# InkTime_schematic.net
KiCad netlist of a schematic drawn in EAGLE
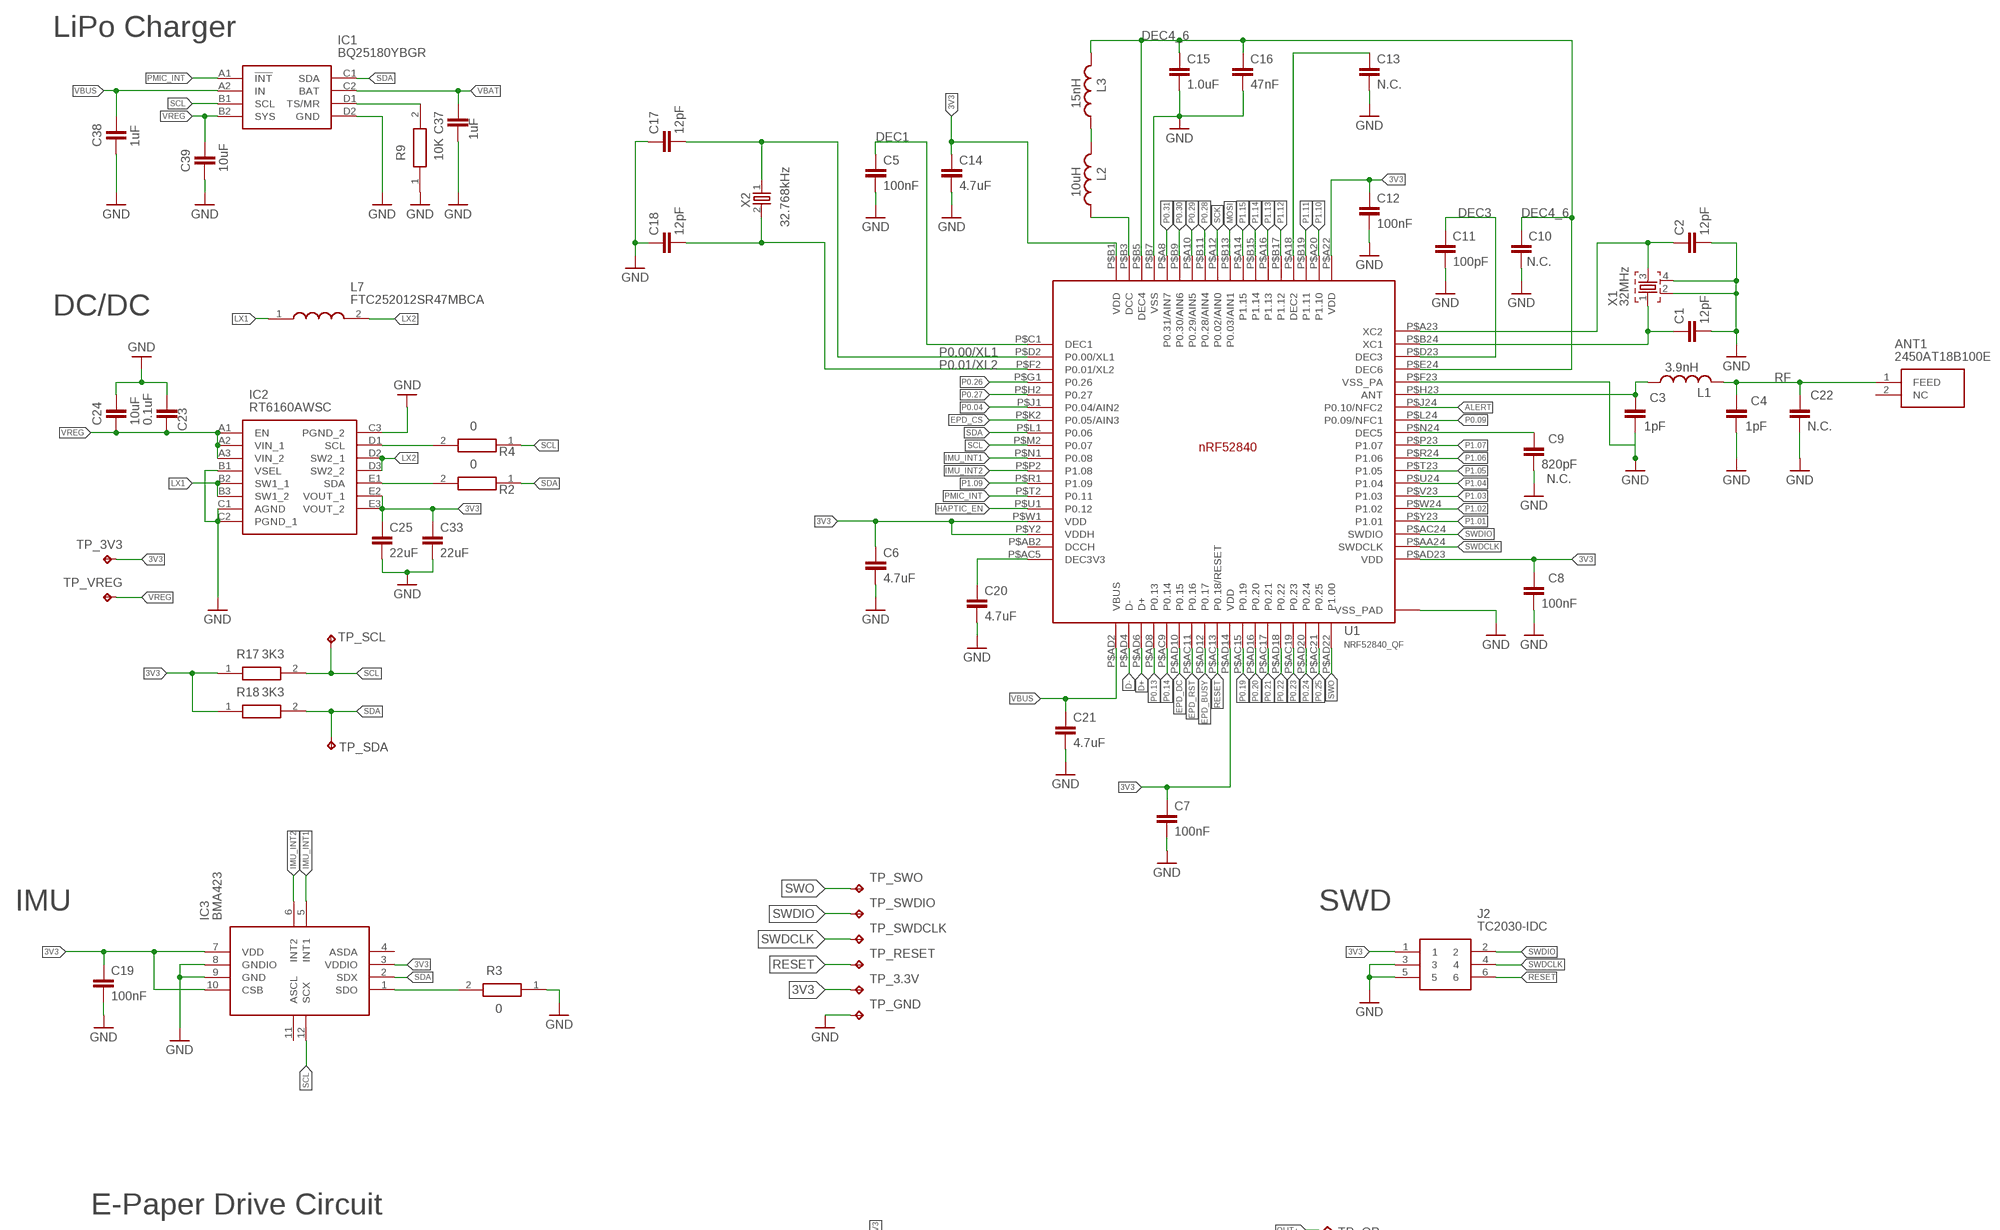
[diagram p0: schematic, sheet 1, part 1 of 2]
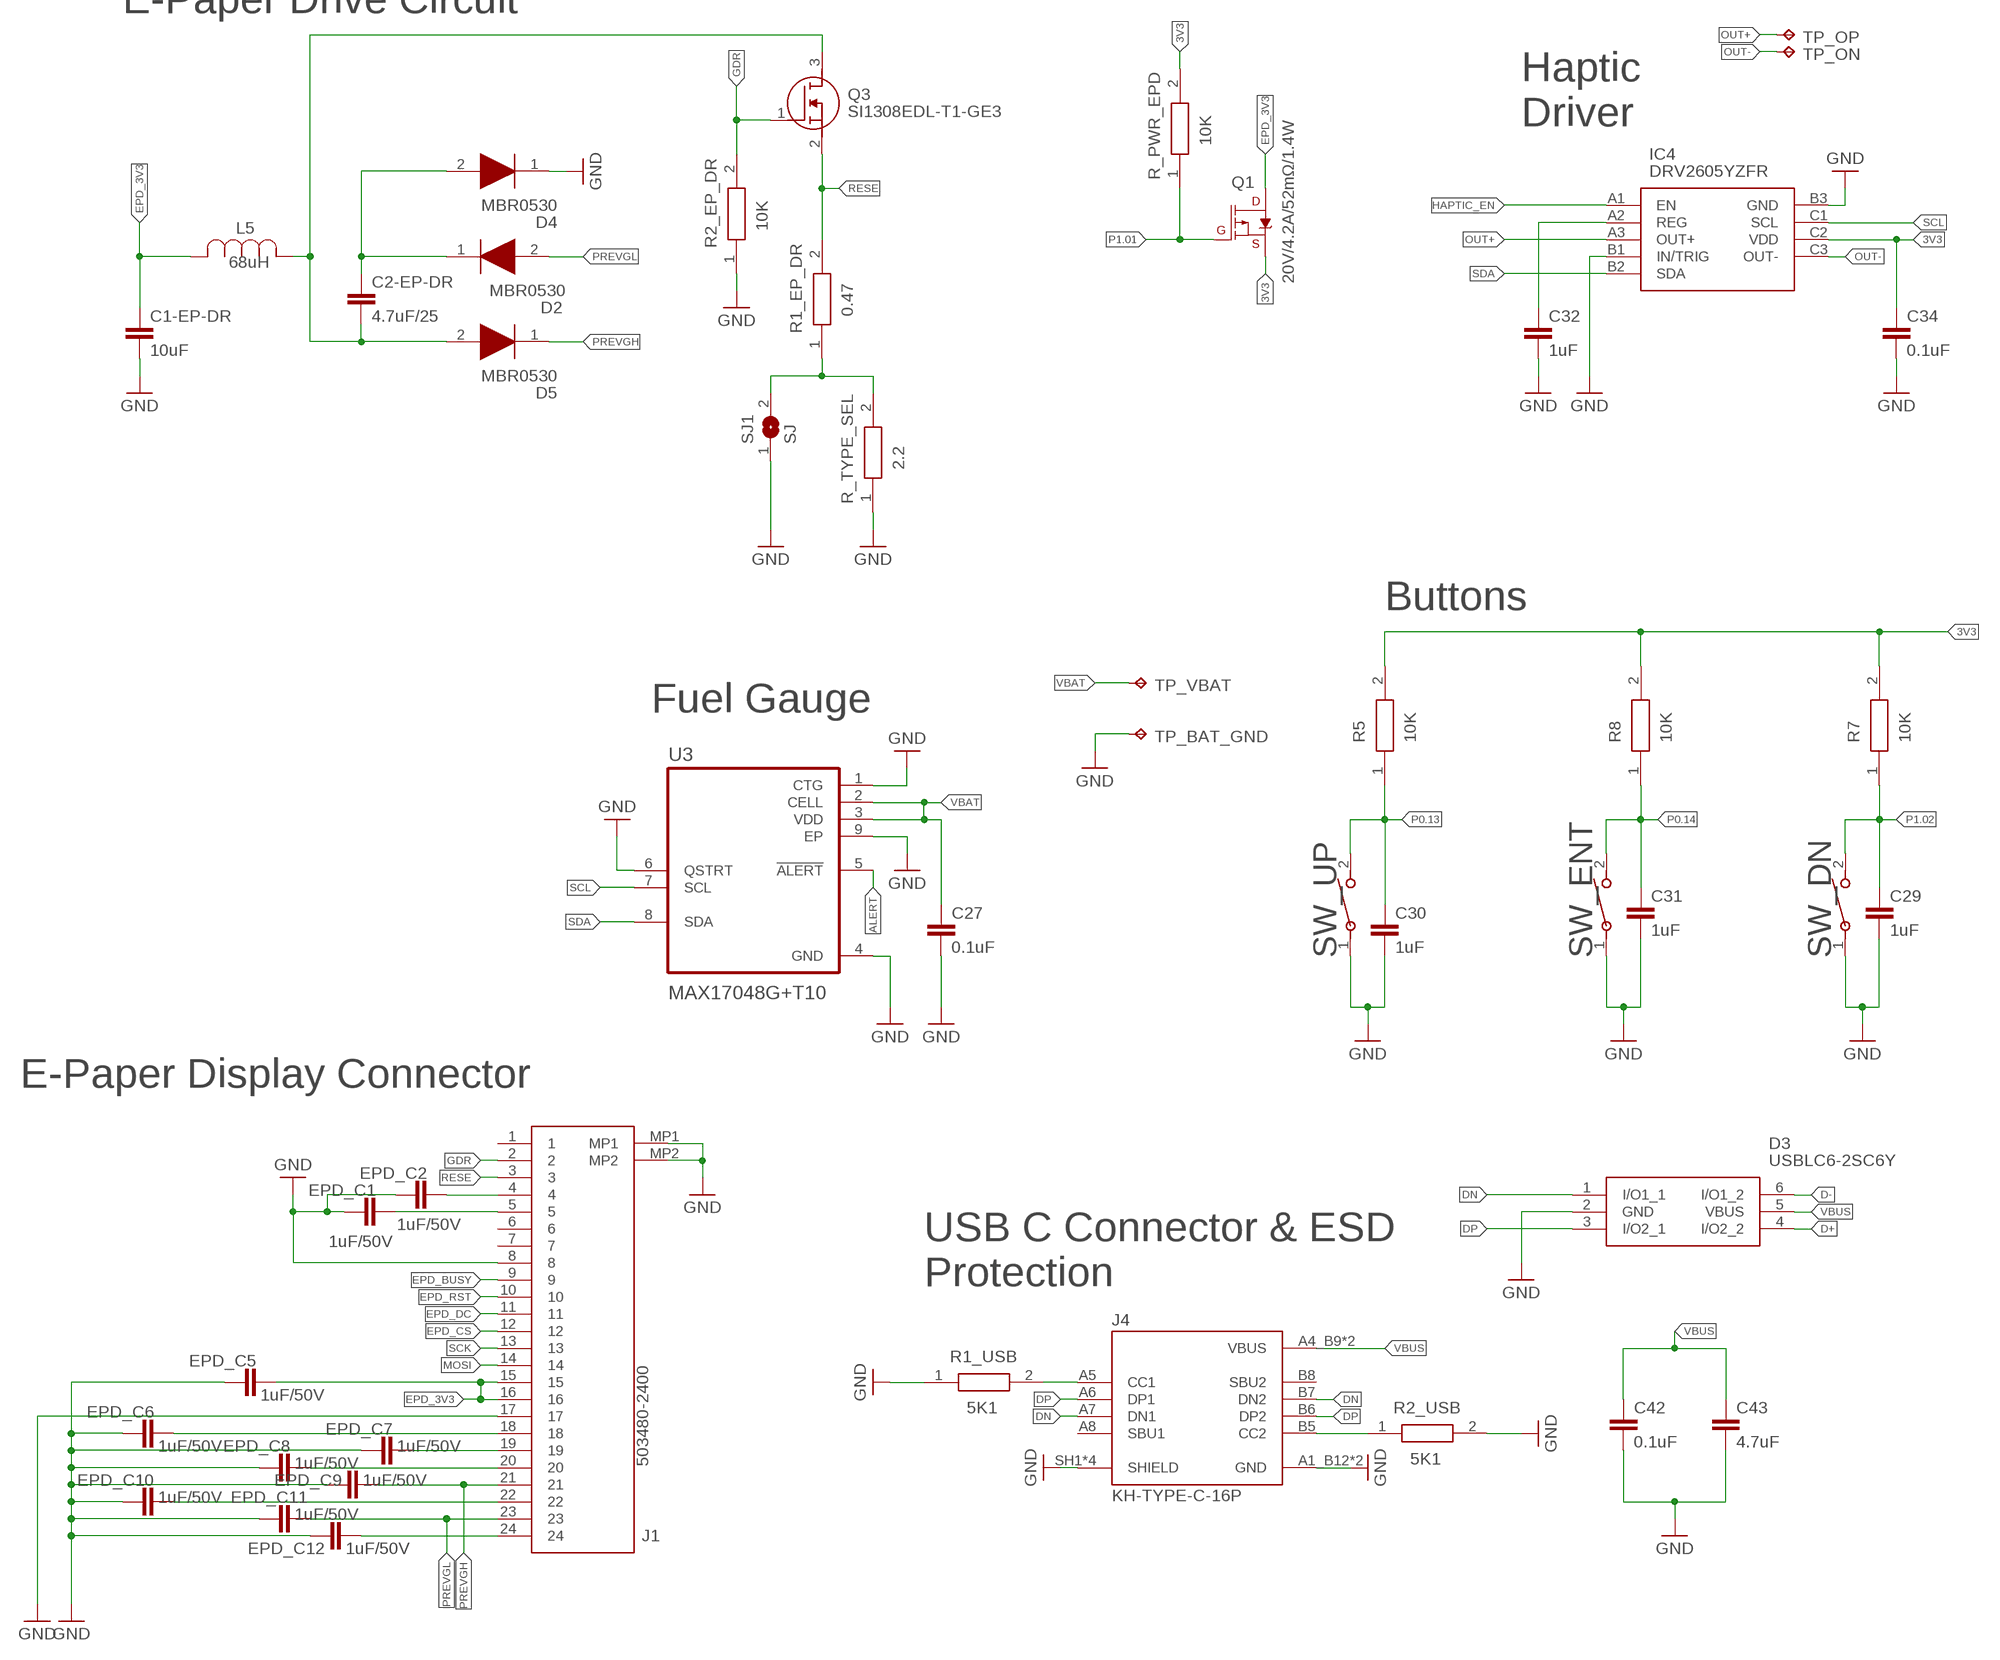
[diagram p1: schematic, sheet 1, part 2 of 2]

(export (version "E")
  (design (tool "Eeschema 10.0.6"))
  (components
    (comp (ref "ANT1")
      (value "2450AT18B100E")
      (footprint "eagle-import:2450AT18B100E_ANTC3216X140N")
      (fields (field (name "MOUSER_PART_NUMBER") "609-2450AT18B100E"))
      (libsource (lib "eagle-import") (part "2450AT18B100E_2450AT18B100E"))
    )
    (comp (ref "C1")
      (value "12pF")
      (footprint "eagle-import:NORDIC_NRF_3_RESC0201_N")
      (libsource (lib "eagle-import") (part "NORDIC_NRF_3_CAPACITOR_0201_N"))
    )
    (comp (ref "C1-EP-DR")
      (value "10uF")
      (footprint "eagle-import:NORDIC_NRF_3_RESC0402_N")
      (libsource (lib "eagle-import") (part "NORDIC_NRF_3_CAPACITOR_0402_N"))
    )
    (comp (ref "C2")
      (value "12pF")
      (footprint "eagle-import:NORDIC_NRF_3_RESC0201_N")
      (libsource (lib "eagle-import") (part "NORDIC_NRF_3_CAPACITOR_0201_N"))
    )
    (comp (ref "C2-EP-DR")
      (value "4.7uF/25")
      (footprint "eagle-import:NORDIC_NRF_3_RESC0603_N")
      (libsource (lib "eagle-import") (part "NORDIC_NRF_3_CAPACITOR_0603_N"))
    )
    (comp (ref "C3")
      (value "1pF")
      (footprint "eagle-import:NORDIC_NRF_3_RESC0201_N")
      (libsource (lib "eagle-import") (part "NORDIC_NRF_3_CAPACITOR_0201_N"))
    )
    (comp (ref "C4")
      (value "1pF")
      (footprint "eagle-import:NORDIC_NRF_3_RESC0201_N")
      (libsource (lib "eagle-import") (part "NORDIC_NRF_3_CAPACITOR_0201_N"))
    )
    (comp (ref "C5")
      (value "100nF")
      (footprint "eagle-import:NORDIC_NRF_3_RESC0201_N")
      (libsource (lib "eagle-import") (part "NORDIC_NRF_3_CAPACITOR_0201_N"))
    )
    (comp (ref "C6")
      (value "4.7uF")
      (footprint "eagle-import:NORDIC_NRF_3_RESC0402_N")
      (libsource (lib "eagle-import") (part "NORDIC_NRF_3_CAPACITOR_0402_N"))
    )
    (comp (ref "C7")
      (value "100nF")
      (footprint "eagle-import:NORDIC_NRF_3_RESC0201_N")
      (libsource (lib "eagle-import") (part "NORDIC_NRF_3_CAPACITOR_0201_N"))
    )
    (comp (ref "C8")
      (value "100nF")
      (footprint "eagle-import:NORDIC_NRF_3_RESC0201_N")
      (libsource (lib "eagle-import") (part "NORDIC_NRF_3_CAPACITOR_0201_N"))
    )
    (comp (ref "C9")
      (value "820pF")
      (footprint "eagle-import:NORDIC_NRF_3_RESC0201_N")
      (libsource (lib "eagle-import") (part "NORDIC_NRF_3_CAPACITOR_0201_N"))
    )
    (comp (ref "C10")
      (value "N.C.")
      (footprint "eagle-import:NORDIC_NRF_3_RESC0201_N")
      (libsource (lib "eagle-import") (part "NORDIC_NRF_3_CAPACITOR_0201_N"))
    )
    (comp (ref "C11")
      (value "100pF")
      (footprint "eagle-import:NORDIC_NRF_3_RESC0201_N")
      (libsource (lib "eagle-import") (part "NORDIC_NRF_3_CAPACITOR_0201_N"))
    )
    (comp (ref "C12")
      (value "100nF")
      (footprint "eagle-import:NORDIC_NRF_3_RESC0201_N")
      (libsource (lib "eagle-import") (part "NORDIC_NRF_3_CAPACITOR_0201_N"))
    )
    (comp (ref "C13")
      (value "N.C.")
      (footprint "eagle-import:NORDIC_NRF_3_RESC0201_N")
      (libsource (lib "eagle-import") (part "NORDIC_NRF_3_CAPACITOR_0201_N"))
    )
    (comp (ref "C14")
      (value "4.7uF")
      (footprint "eagle-import:NORDIC_NRF_3_RESC0402_N")
      (libsource (lib "eagle-import") (part "NORDIC_NRF_3_CAPACITOR_0402_N"))
    )
    (comp (ref "C15")
      (value "1.0uF")
      (footprint "eagle-import:NORDIC_NRF_3_RESC0402_N")
      (libsource (lib "eagle-import") (part "NORDIC_NRF_3_CAPACITOR_0402_N"))
    )
    (comp (ref "C16")
      (value "47nF")
      (footprint "eagle-import:NORDIC_NRF_3_RESC0201_N")
      (libsource (lib "eagle-import") (part "NORDIC_NRF_3_CAPACITOR_0201_N"))
    )
    (comp (ref "C17")
      (value "12pF")
      (footprint "eagle-import:NORDIC_NRF_3_RESC0201_N")
      (libsource (lib "eagle-import") (part "NORDIC_NRF_3_CAPACITOR_0201_N"))
    )
    (comp (ref "C18")
      (value "12pF")
      (footprint "eagle-import:NORDIC_NRF_3_RESC0201_N")
      (libsource (lib "eagle-import") (part "NORDIC_NRF_3_CAPACITOR_0201_N"))
    )
    (comp (ref "C19")
      (value "100nF")
      (footprint "eagle-import:NORDIC_NRF_3_RESC0201_N")
      (libsource (lib "eagle-import") (part "NORDIC_NRF_3_CAPACITOR_0201_N"))
    )
    (comp (ref "C20")
      (value "4.7uF")
      (footprint "eagle-import:NORDIC_NRF_3_RESC0402_N")
      (libsource (lib "eagle-import") (part "NORDIC_NRF_3_CAPACITOR_0402_N"))
    )
    (comp (ref "C21")
      (value "4.7uF")
      (footprint "eagle-import:NORDIC_NRF_3_RESC0402_N")
      (libsource (lib "eagle-import") (part "NORDIC_NRF_3_CAPACITOR_0402_N"))
    )
    (comp (ref "C22")
      (value "N.C.")
      (footprint "eagle-import:NORDIC_NRF_3_RESC0201_N")
      (libsource (lib "eagle-import") (part "NORDIC_NRF_3_CAPACITOR_0201_N"))
    )
    (comp (ref "C23")
      (value "0.1uF")
      (footprint "eagle-import:NORDIC_NRF_3_RESC0201_N")
      (libsource (lib "eagle-import") (part "NORDIC_NRF_3_CAPACITOR_0201_N"))
    )
    (comp (ref "C24")
      (value "10uF")
      (footprint "eagle-import:NORDIC_NRF_3_RESC0402_N")
      (libsource (lib "eagle-import") (part "NORDIC_NRF_3_CAPACITOR_0402_N"))
    )
    (comp (ref "C25")
      (value "22uF")
      (footprint "eagle-import:NORDIC_NRF_3_RESC0402_N")
      (libsource (lib "eagle-import") (part "NORDIC_NRF_3_CAPACITOR_0402_N"))
    )
    (comp (ref "C27")
      (value "0.1uF")
      (footprint "eagle-import:NORDIC_NRF_3_RESC0201_N")
      (libsource (lib "eagle-import") (part "NORDIC_NRF_3_CAPACITOR_0201_N"))
    )
    (comp (ref "C29")
      (value "1uF")
      (footprint "eagle-import:NORDIC_NRF_3_RESC0402_N")
      (libsource (lib "eagle-import") (part "NORDIC_NRF_3_CAPACITOR_0402_N"))
    )
    (comp (ref "C30")
      (value "1uF")
      (footprint "eagle-import:NORDIC_NRF_3_RESC0402_N")
      (libsource (lib "eagle-import") (part "NORDIC_NRF_3_CAPACITOR_0402_N"))
    )
    (comp (ref "C31")
      (value "1uF")
      (footprint "eagle-import:NORDIC_NRF_3_RESC0402_N")
      (libsource (lib "eagle-import") (part "NORDIC_NRF_3_CAPACITOR_0402_N"))
    )
    (comp (ref "C32")
      (value "1uF")
      (footprint "eagle-import:NORDIC_NRF_3_RESC0402_N")
      (libsource (lib "eagle-import") (part "NORDIC_NRF_3_CAPACITOR_0402_N"))
    )
    (comp (ref "C33")
      (value "22uF")
      (footprint "eagle-import:NORDIC_NRF_3_RESC0402_N")
      (libsource (lib "eagle-import") (part "NORDIC_NRF_3_CAPACITOR_0402_N"))
    )
    (comp (ref "C34")
      (value "0.1uF")
      (footprint "eagle-import:NORDIC_NRF_3_RESC0201_N")
      (libsource (lib "eagle-import") (part "NORDIC_NRF_3_CAPACITOR_0201_N"))
    )
    (comp (ref "C37")
      (value "1uF")
      (footprint "eagle-import:NORDIC_NRF_3_RESC0402_N")
      (libsource (lib "eagle-import") (part "NORDIC_NRF_3_CAPACITOR_0402_N"))
    )
    (comp (ref "C38")
      (value "1uF")
      (footprint "eagle-import:NORDIC_NRF_3_RESC0402_N")
      (libsource (lib "eagle-import") (part "NORDIC_NRF_3_CAPACITOR_0402_N"))
    )
    (comp (ref "C39")
      (value "10uF")
      (footprint "eagle-import:NORDIC_NRF_3_RESC0402_N")
      (libsource (lib "eagle-import") (part "NORDIC_NRF_3_CAPACITOR_0402_N"))
    )
    (comp (ref "C42")
      (value "0.1uF")
      (footprint "eagle-import:NORDIC_NRF_3_RESC0201_N")
      (libsource (lib "eagle-import") (part "NORDIC_NRF_3_CAPACITOR_0201_N"))
    )
    (comp (ref "C43")
      (value "4.7uF")
      (footprint "eagle-import:NORDIC_NRF_3_RESC0402_N")
      (libsource (lib "eagle-import") (part "NORDIC_NRF_3_CAPACITOR_0402_N"))
    )
    (comp (ref "D2")
      (value "MBR0530")
      (footprint "eagle-import:ESP32_C6_LIBRARY_5_SOD3716X135N")
      (fields (field (name "MF") "ON Semiconductor"))
      (libsource (lib "eagle-import") (part "ESP32_C6_LIBRARY_5_MBR0530"))
    )
    (comp (ref "D3")
      (value "USBLC6-2SC6Y")
      (footprint "eagle-import:ESP32_C6_LIBRARY_3_SOT95P280X145-6N")
      (fields (field (name "MF") "STMicroelectronics"))
      (libsource (lib "eagle-import") (part "ESP32_C6_LIBRARY_3_USBLC6-2SC6Y"))
    )
    (comp (ref "D4")
      (value "MBR0530")
      (footprint "eagle-import:ESP32_C6_LIBRARY_5_SOD3716X135N")
      (fields (field (name "MF") "ON Semiconductor"))
      (libsource (lib "eagle-import") (part "ESP32_C6_LIBRARY_5_MBR0530"))
    )
    (comp (ref "D5")
      (value "MBR0530")
      (footprint "eagle-import:ESP32_C6_LIBRARY_5_SOD3716X135N")
      (fields (field (name "MF") "ON Semiconductor"))
      (libsource (lib "eagle-import") (part "ESP32_C6_LIBRARY_5_MBR0530"))
    )
    (comp (ref "EPD_C1")
      (value "1uF/50V")
      (footprint "eagle-import:NORDIC_NRF_3_RESC0603_N")
      (libsource (lib "eagle-import") (part "NORDIC_NRF_3_CAPACITOR_0603_N"))
    )
    (comp (ref "EPD_C2")
      (value "1uF/50V")
      (footprint "eagle-import:NORDIC_NRF_3_RESC0603_N")
      (libsource (lib "eagle-import") (part "NORDIC_NRF_3_CAPACITOR_0603_N"))
    )
    (comp (ref "EPD_C5")
      (value "1uF/50V")
      (footprint "eagle-import:NORDIC_NRF_3_RESC0603_N")
      (libsource (lib "eagle-import") (part "NORDIC_NRF_3_CAPACITOR_0603_N"))
    )
    (comp (ref "EPD_C6")
      (value "1uF/50V")
      (footprint "eagle-import:NORDIC_NRF_3_RESC0603_N")
      (libsource (lib "eagle-import") (part "NORDIC_NRF_3_CAPACITOR_0603_N"))
    )
    (comp (ref "EPD_C7")
      (value "1uF/50V")
      (footprint "eagle-import:NORDIC_NRF_3_RESC0603_N")
      (libsource (lib "eagle-import") (part "NORDIC_NRF_3_CAPACITOR_0603_N"))
    )
    (comp (ref "EPD_C8")
      (value "1uF/50V")
      (footprint "eagle-import:NORDIC_NRF_3_RESC0603_N")
      (libsource (lib "eagle-import") (part "NORDIC_NRF_3_CAPACITOR_0603_N"))
    )
    (comp (ref "EPD_C9")
      (value "1uF/50V")
      (footprint "eagle-import:NORDIC_NRF_3_RESC0603_N")
      (libsource (lib "eagle-import") (part "NORDIC_NRF_3_CAPACITOR_0603_N"))
    )
    (comp (ref "EPD_C10")
      (value "1uF/50V")
      (footprint "eagle-import:NORDIC_NRF_3_RESC0603_N")
      (libsource (lib "eagle-import") (part "NORDIC_NRF_3_CAPACITOR_0603_N"))
    )
    (comp (ref "EPD_C11")
      (value "1uF/50V")
      (footprint "eagle-import:NORDIC_NRF_3_RESC0603_N")
      (libsource (lib "eagle-import") (part "NORDIC_NRF_3_CAPACITOR_0603_N"))
    )
    (comp (ref "EPD_C12")
      (value "1uF/50V")
      (footprint "eagle-import:NORDIC_NRF_3_RESC0603_N")
      (libsource (lib "eagle-import") (part "NORDIC_NRF_3_CAPACITOR_0603_N"))
    )
    (comp (ref "IC1")
      (value "BQ25180YBGR")
      (footprint "eagle-import:BQ25180YBGR_BGA8C40P2X4_100X155X50")
      (fields (field (name "MOUSER_PART_NUMBER") "595-BQ25180YBGR"))
      (libsource (lib "eagle-import") (part "BQ25180YBGR_BQ25180YBGR"))
    )
    (comp (ref "IC2")
      (value "RT6160AWSC")
      (footprint "eagle-import:RT6160AWSC_BGA15C40P3X5_140X230X60")
      (fields (field (name "MOUSER_PART_NUMBER") "835-RT6160AWSC"))
      (libsource (lib "eagle-import") (part "RT6160AWSC_RT6160AWSC"))
    )
    (comp (ref "IC3")
      (value "BMA423")
      (footprint "eagle-import:BMA423_BMA423")
      (fields (field (name "MOUSER_PART_NUMBER") "262-BMA423"))
      (libsource (lib "eagle-import") (part "BMA423_BMA423"))
    )
    (comp (ref "IC4")
      (value "DRV2605YZFR")
      (footprint "eagle-import:DRV2605YZFR_BGA9C50P3X3_144X144X62")
      (libsource (lib "eagle-import") (part "DRV2605YZFR_DRV2605YZFR"))
    )
    (comp (ref "J1")
      (value "503480-2400")
      (footprint "eagle-import:503480-2400_5034802400")
      (fields (field (name "MOUSER_PART_NUMBER") "538-503480-2400"))
      (libsource (lib "eagle-import") (part "503480-2400_503480-2400"))
    )
    (comp (ref "J2")
      (value "TC2030-IDC")
      (footprint "eagle-import:TC2030-IDC_TC2030IDC")
      (libsource (lib "eagle-import") (part "TC2030-IDC_TC2030-IDC"))
    )
    (comp (ref "J4")
      (value "KH-TYPE-C-16P")
      (footprint "eagle-import:KH-TYPE-C-16P_KINGHELM_KH-TYPE-C-16P")
      (fields (field (name "MF") "kinghelm"))
      (libsource (lib "eagle-import") (part "KH-TYPE-C-16P_KH-TYPE-C-16P"))
    )
    (comp (ref "L1")
      (value "3.9nH")
      (footprint "eagle-import:NORDIC_NRF_2_RESC0201_N")
      (libsource (lib "eagle-import") (part "NORDIC_NRF_2_INDUCTOR_0201_N"))
    )
    (comp (ref "L2")
      (value "10uH")
      (footprint "eagle-import:NORDIC_NRF_2_RESC0201_N")
      (libsource (lib "eagle-import") (part "NORDIC_NRF_2_INDUCTOR_0201_N"))
    )
    (comp (ref "L3")
      (value "15nH")
      (footprint "eagle-import:NORDIC_NRF_2_RESC0201_N")
      (libsource (lib "eagle-import") (part "NORDIC_NRF_2_INDUCTOR_0201_N"))
    )
    (comp (ref "L5")
      (value "68uH")
      (footprint "eagle-import:ESP32_C6_LIBRARY_2_IND_4828-WE-TPC_WRE")
      (fields
        (field (name "MANUFACTURER_PART_NUMBER") "744043680")
        (field (name "COPYRIGHT") "Copyright (C) 2024 Ultra Librarian. All rights reserved.")
      )
      (libsource (lib "eagle-import") (part "ESP32_C6_LIBRARY_2_744043680IND_4828-WE-TPC_WRE"))
    )
    (comp (ref "L7")
      (value "FTC252012SR47MBCA")
      (footprint "eagle-import:MLP2016SR47MT0S1_INDC2016X100N")
      (libsource (lib "eagle-import") (part "MLP2016SR47MT0S1_FTC252012SR47MBCA"))
    )
    (comp (ref "Q1")
      (value "20V/4.2A/52mΩ/1.4W")
      (footprint "eagle-import:ESP32_C6_LIBRARY_4_ESP32_C6_LIBRARY_4_ESP32_C6_LIBRARY_4_ESP32_C6_LIBRARY_4_ESP32_WROVER_SPARKFUN-DISCRETESEMI_SOT23-3")
      (libsource (lib "eagle-import") (part "ESP32_C6_LIBRARY_4_ESP32_WROVER_SPARKFUN-DISCRETESEMI_MOSFET_PCH-DMG2305UX-7"))
    )
    (comp (ref "Q3")
      (value "SI1308EDL-T1-GE3")
      (footprint "eagle-import:ESP32_C6_LIBRARY_6_SOT65P210X110-3N")
      (fields (field (name "MF") "Vishay Siliconix"))
      (libsource (lib "eagle-import") (part "ESP32_C6_LIBRARY_6_SI1308EDL-T1-GE3"))
    )
    (comp (ref "R1_EP_DR")
      (value "0.47")
      (footprint "eagle-import:ERA-1AEB3401C_0201")
      (libsource (lib "eagle-import") (part "ERA-1AEB3401C_CPF0201D7K68C1"))
    )
    (comp (ref "R1_USB")
      (value "5K1")
      (footprint "eagle-import:CPF0201D7K68C1_0201")
      (libsource (lib "eagle-import") (part "CPF0201D7K68C1_CPF0201D7K68C1"))
    )
    (comp (ref "R2")
      (value "0")
      (footprint "eagle-import:CPF0201D7K68C1_0201")
      (libsource (lib "eagle-import") (part "CPF0201D7K68C1_CPF0201D7K68C1"))
    )
    (comp (ref "R2_EP_DR")
      (value "10K")
      (footprint "eagle-import:ERA-1AEB3401C_0201")
      (libsource (lib "eagle-import") (part "ERA-1AEB3401C_CPF0201D7K68C1"))
    )
    (comp (ref "R2_USB")
      (value "5K1")
      (footprint "eagle-import:CPF0201D7K68C1_0201")
      (libsource (lib "eagle-import") (part "CPF0201D7K68C1_CPF0201D7K68C1"))
    )
    (comp (ref "R3")
      (value "0")
      (footprint "eagle-import:ERA-1AEB3401C_0201")
      (libsource (lib "eagle-import") (part "ERA-1AEB3401C_CPF0201D7K68C1"))
    )
    (comp (ref "R4")
      (value "0")
      (footprint "eagle-import:CPF0201D7K68C1_0201")
      (libsource (lib "eagle-import") (part "CPF0201D7K68C1_CPF0201D7K68C1"))
    )
    (comp (ref "R5")
      (value "10K")
      (footprint "eagle-import:ERA-1AEB3401C_0201")
      (libsource (lib "eagle-import") (part "ERA-1AEB3401C_CPF0201D7K68C1"))
    )
    (comp (ref "R7")
      (value "10K")
      (footprint "eagle-import:ERA-1AEB3401C_0201")
      (libsource (lib "eagle-import") (part "ERA-1AEB3401C_CPF0201D7K68C1"))
    )
    (comp (ref "R8")
      (value "10K")
      (footprint "eagle-import:ERA-1AEB3401C_0201")
      (libsource (lib "eagle-import") (part "ERA-1AEB3401C_CPF0201D7K68C1"))
    )
    (comp (ref "R9")
      (value "10K")
      (footprint "eagle-import:CPF0201D7K68C1_0201")
      (libsource (lib "eagle-import") (part "CPF0201D7K68C1_CPF0201D7K68C1"))
    )
    (comp (ref "R17")
      (value "3K3")
      (footprint "eagle-import:CPF0201D7K68C1_0201")
      (libsource (lib "eagle-import") (part "CPF0201D7K68C1_CPF0201D7K68C1"))
    )
    (comp (ref "R18")
      (value "3K3")
      (footprint "eagle-import:CPF0201D7K68C1_0201")
      (libsource (lib "eagle-import") (part "CPF0201D7K68C1_CPF0201D7K68C1"))
    )
    (comp (ref "R_PWR_EPD")
      (value "10K")
      (footprint "eagle-import:CPF0201D7K68C1_0201")
      (libsource (lib "eagle-import") (part "CPF0201D7K68C1_CPF0201D7K68C1"))
    )
    (comp (ref "R_TYPE_SEL")
      (value "2.2")
      (footprint "eagle-import:ERA-1AEB3401C_0201")
      (libsource (lib "eagle-import") (part "ERA-1AEB3401C_CPF0201D7K68C1"))
    )
    (comp (ref "SJ1")
      (value "SJ")
      (footprint "eagle-import:ESP32_C6_LIBRARY_7_JUMPER_SJ")
      (libsource (lib "eagle-import") (part "ESP32_C6_LIBRARY_7_JUMPER_SJ"))
    )
    (comp (ref "SW_DN")
      (value "SW_DN")
      (footprint "eagle-import:2025-10-22_07-23-44_LIBRARY_SW_EVP-AKE31A_PAN")
      (fields
        (field (name "MANUFACTURER_PART_NUMBER") "EVP-AKE31A")
        (field (name "COPYRIGHT") "Copyright (C) 2025 Ultra Librarian. All rights reserved.")
      )
      (libsource (lib "eagle-import") (part "2025-10-22_07-23-44_LIBRARY_EVP-AKE31ASW_EVP-AKE31A_PAN"))
    )
    (comp (ref "SW_ENT")
      (value "SW_ENT")
      (footprint "eagle-import:2025-10-22_07-23-44_LIBRARY_SW_EVP-AKE31A_PAN")
      (fields
        (field (name "MANUFACTURER_PART_NUMBER") "EVP-AKE31A")
        (field (name "COPYRIGHT") "Copyright (C) 2025 Ultra Librarian. All rights reserved.")
      )
      (libsource (lib "eagle-import") (part "2025-10-22_07-23-44_LIBRARY_EVP-AKE31ASW_EVP-AKE31A_PAN"))
    )
    (comp (ref "SW_UP")
      (value "SW_UP")
      (footprint "eagle-import:2025-10-22_07-23-44_LIBRARY_SW_EVP-AKE31A_PAN")
      (fields
        (field (name "MANUFACTURER_PART_NUMBER") "EVP-AKE31A")
        (field (name "COPYRIGHT") "Copyright (C) 2025 Ultra Librarian. All rights reserved.")
      )
      (libsource (lib "eagle-import") (part "2025-10-22_07-23-44_LIBRARY_EVP-AKE31ASW_EVP-AKE31A_PAN"))
    )
    (comp (ref "TP_3.3V")
      (value "HECTOR_WATCH_1_TPTP20R")
      (footprint "eagle-import:HECTOR_WATCH_1_TP20R")
      (libsource (lib "eagle-import") (part "HECTOR_WATCH_1_TPTP20R"))
    )
    (comp (ref "TP_3V3")
      (value "HECTOR_WATCH_1_TPTP20R")
      (footprint "eagle-import:HECTOR_WATCH_1_TP20R")
      (libsource (lib "eagle-import") (part "HECTOR_WATCH_1_TPTP20R"))
    )
    (comp (ref "TP_BAT_GND")
      (value "HECTOR_WATCH_1_TPTP20R")
      (footprint "eagle-import:HECTOR_WATCH_1_TP20R")
      (libsource (lib "eagle-import") (part "HECTOR_WATCH_1_TPTP20R"))
    )
    (comp (ref "TP_GND")
      (value "HECTOR_WATCH_1_TPTP20R")
      (footprint "eagle-import:HECTOR_WATCH_1_TP20R")
      (libsource (lib "eagle-import") (part "HECTOR_WATCH_1_TPTP20R"))
    )
    (comp (ref "TP_ON")
      (value "HECTOR_WATCH_1_TPTP20R")
      (footprint "eagle-import:HECTOR_WATCH_1_TP20R")
      (libsource (lib "eagle-import") (part "HECTOR_WATCH_1_TPTP20R"))
    )
    (comp (ref "TP_OP")
      (value "HECTOR_WATCH_1_TPTP20R")
      (footprint "eagle-import:HECTOR_WATCH_1_TP20R")
      (libsource (lib "eagle-import") (part "HECTOR_WATCH_1_TPTP20R"))
    )
    (comp (ref "TP_RESET")
      (value "HECTOR_WATCH_1_TPTP20R")
      (footprint "eagle-import:HECTOR_WATCH_1_TP20R")
      (libsource (lib "eagle-import") (part "HECTOR_WATCH_1_TPTP20R"))
    )
    (comp (ref "TP_SCL")
      (value "HECTOR_WATCH_1_TPTP20R")
      (footprint "eagle-import:HECTOR_WATCH_1_TP20R")
      (libsource (lib "eagle-import") (part "HECTOR_WATCH_1_TPTP20R"))
    )
    (comp (ref "TP_SDA")
      (value "HECTOR_WATCH_1_TPTP20R")
      (footprint "eagle-import:HECTOR_WATCH_1_TP20R")
      (libsource (lib "eagle-import") (part "HECTOR_WATCH_1_TPTP20R"))
    )
    (comp (ref "TP_SWDCLK")
      (value "HECTOR_WATCH_1_TPTP20R")
      (footprint "eagle-import:HECTOR_WATCH_1_TP20R")
      (libsource (lib "eagle-import") (part "HECTOR_WATCH_1_TPTP20R"))
    )
    (comp (ref "TP_SWDIO")
      (value "HECTOR_WATCH_1_TPTP20R")
      (footprint "eagle-import:HECTOR_WATCH_1_TP20R")
      (libsource (lib "eagle-import") (part "HECTOR_WATCH_1_TPTP20R"))
    )
    (comp (ref "TP_SWO")
      (value "HECTOR_WATCH_1_TPTP20R")
      (footprint "eagle-import:HECTOR_WATCH_1_TP20R")
      (libsource (lib "eagle-import") (part "HECTOR_WATCH_1_TPTP20R"))
    )
    (comp (ref "TP_VBAT")
      (value "HECTOR_WATCH_1_TPTP20R")
      (footprint "eagle-import:HECTOR_WATCH_1_TP20R")
      (libsource (lib "eagle-import") (part "HECTOR_WATCH_1_TPTP20R"))
    )
    (comp (ref "TP_VREG")
      (value "HECTOR_WATCH_1_TPTP20R")
      (footprint "eagle-import:HECTOR_WATCH_1_TP20R")
      (libsource (lib "eagle-import") (part "HECTOR_WATCH_1_TPTP20R"))
    )
    (comp (ref "U1")
      (value "NRF52840_QF")
      (footprint "eagle-import:NORDIC_NRF_4_AQFN50P700X700X85_HS-74N")
      (libsource (lib "eagle-import") (part "NORDIC_NRF_4_NRF52840_QF"))
    )
    (comp (ref "U3")
      (value "MAX17048G+T10")
      (footprint "eagle-import:ESP32_C6_LIBRARY_SON50P200X200X80-9N")
      (fields (field (name "MF") "Analog Devices"))
      (libsource (lib "eagle-import") (part "ESP32_C6_LIBRARY_MAX17048G+T10"))
    )
    (comp (ref "X1")
      (value "32MHz")
      (footprint "eagle-import:NORDIC_NRF_BT-XTAL_2016_N")
      (libsource (lib "eagle-import") (part "NORDIC_NRF_XTAL_32MHZ"))
    )
    (comp (ref "X2")
      (value "32.768kHz")
      (footprint "eagle-import:NORDIC_NRF_1_XTAL_3215_N")
      (libsource (lib "eagle-import") (part "NORDIC_NRF_1_XTAL_32KHZ"))
    )
  )
  (nets
    (net (code "1") (name "/DEC1") (class "Default")
      (node (ref "C5") (pin "1") (pinfunction "1_1") (pintype "passive"))
      (node (ref "U1") (pin "P$C1") (pinfunction "DEC1_P$C1") (pintype "power_in"))
    )
    (net (code "2") (name "/DEC3") (class "Default")
      (node (ref "C11") (pin "2") (pinfunction "2_2") (pintype "passive"))
      (node (ref "U1") (pin "P$D23") (pinfunction "DEC3_P$D23") (pintype "bidirectional"))
    )
    (net (code "3") (name "/DEC4_6") (class "Default")
      (node (ref "C10") (pin "2") (pinfunction "2_2") (pintype "passive"))
      (node (ref "C15") (pin "1") (pinfunction "1_1") (pintype "passive"))
      (node (ref "C16") (pin "1") (pinfunction "1_1") (pintype "passive"))
      (node (ref "L3") (pin "2") (pinfunction "2_2") (pintype "passive"))
      (node (ref "U1") (pin "P$B5") (pinfunction "DEC4_P$B5") (pintype "power_in"))
      (node (ref "U1") (pin "P$E24") (pinfunction "DEC6_P$E24") (pintype "bidirectional"))
    )
    (net (code "4") (name "/P0.00{slash}XL1") (class "Default")
      (node (ref "C17") (pin "2") (pinfunction "2_2") (pintype "passive"))
      (node (ref "U1") (pin "P$D2") (pinfunction "P0.00/XL1_P$D2") (pintype "bidirectional"))
      (node (ref "X2") (pin "1") (pinfunction "1_1") (pintype "passive"))
    )
    (net (code "5") (name "/P0.01{slash}XL2") (class "Default")
      (node (ref "C18") (pin "2") (pinfunction "2_2") (pintype "passive"))
      (node (ref "U1") (pin "P$F2") (pinfunction "P0.01/XL2_P$F2") (pintype "bidirectional"))
      (node (ref "X2") (pin "2") (pinfunction "2_2") (pintype "passive"))
    )
    (net (code "6") (name "/RF") (class "Default")
      (node (ref "ANT1") (pin "1") (pinfunction "FEED_1") (pintype "input"))
      (node (ref "C22") (pin "1") (pinfunction "1_1") (pintype "passive"))
      (node (ref "C4") (pin "2") (pinfunction "2_2") (pintype "passive"))
      (node (ref "L1") (pin "2") (pinfunction "2_2") (pintype "passive"))
    )
    (net (code "7") (name "3V3") (class "Default")
      (node (ref "C12") (pin "1") (pinfunction "1_1") (pintype "passive"))
      (node (ref "C14") (pin "1") (pinfunction "1_1") (pintype "passive"))
      (node (ref "C19") (pin "1") (pinfunction "1_1") (pintype "passive"))
      (node (ref "C25") (pin "1") (pinfunction "1_1") (pintype "passive"))
      (node (ref "C33") (pin "1") (pinfunction "1_1") (pintype "passive"))
      (node (ref "C34") (pin "1") (pinfunction "1_1") (pintype "passive"))
      (node (ref "C6") (pin "1") (pinfunction "1_1") (pintype "passive"))
      (node (ref "C7") (pin "1") (pinfunction "1_1") (pintype "passive"))
      (node (ref "C8") (pin "2") (pinfunction "2_2") (pintype "passive"))
      (node (ref "IC2") (pin "E2") (pinfunction "VOUT_1_E2") (pintype "bidirectional"))
      (node (ref "IC2") (pin "E3") (pinfunction "VOUT_2_E3") (pintype "bidirectional"))
      (node (ref "IC3") (pin "10") (pinfunction "CSB_10") (pintype "bidirectional"))
      (node (ref "IC3") (pin "3") (pinfunction "VDDIO_3") (pintype "bidirectional"))
      (node (ref "IC3") (pin "7") (pinfunction "VDD_7") (pintype "bidirectional"))
      (node (ref "IC4") (pin "C2") (pinfunction "VDD_C2") (pintype "bidirectional"))
      (node (ref "J2") (pin "1") (pinfunction "1_1") (pintype "bidirectional"))
      (node (ref "Q1") (pin "2") (pinfunction "S_2") (pintype "bidirectional"))
      (node (ref "R17") (pin "1") (pinfunction "1_1") (pintype "bidirectional"))
      (node (ref "R18") (pin "1") (pinfunction "1_1") (pintype "bidirectional"))
      (node (ref "R5") (pin "2") (pinfunction "2_2") (pintype "bidirectional"))
      (node (ref "R7") (pin "2") (pinfunction "2_2") (pintype "bidirectional"))
      (node (ref "R8") (pin "2") (pinfunction "2_2") (pintype "bidirectional"))
      (node (ref "R_PWR_EPD") (pin "2") (pinfunction "2_2") (pintype "bidirectional"))
      (node (ref "TP_3.3V") (pin "TP") (pinfunction "TP_TP") (pintype "input"))
      (node (ref "TP_3V3") (pin "TP") (pinfunction "TP_TP") (pintype "input"))
      (node (ref "U1") (pin "P$A22") (pinfunction "VDD_P$A22") (pintype "power_in"))
      (node (ref "U1") (pin "P$AD14") (pinfunction "VDD_P$AD14") (pintype "power_in"))
      (node (ref "U1") (pin "P$AD23") (pinfunction "VDD_P$AD23") (pintype "power_in"))
      (node (ref "U1") (pin "P$B1") (pinfunction "VDD_P$B1") (pintype "power_in"))
      (node (ref "U1") (pin "P$W1") (pinfunction "VDD_P$W1") (pintype "power_in"))
      (node (ref "U1") (pin "P$Y2") (pinfunction "VDDH_P$Y2") (pintype "power_in"))
    )
    (net (code "8") (name "ALERT") (class "Default")
      (node (ref "U1") (pin "P$J24") (pinfunction "P0.10/NFC2_P$J24") (pintype "bidirectional"))
      (node (ref "U3") (pin "5") (pinfunction "~{ALERT}_5") (pintype "output"))
    )
    (net (code "9") (name "D+") (class "Default")
      (node (ref "D3") (pin "4") (pinfunction "I/O2_2_4") (pintype "bidirectional"))
      (node (ref "U1") (pin "P$AD6") (pinfunction "D+_P$AD6") (pintype "bidirectional"))
    )
    (net (code "10") (name "D-") (class "Default")
      (node (ref "D3") (pin "6") (pinfunction "I/O1_2_6") (pintype "bidirectional"))
      (node (ref "U1") (pin "P$AD4") (pinfunction "D-_P$AD4") (pintype "bidirectional"))
    )
    (net (code "11") (name "DN") (class "Default")
      (node (ref "D3") (pin "1") (pinfunction "I/O1_1_1") (pintype "bidirectional"))
      (node (ref "J4") (pin "A7") (pinfunction "DN1_A7") (pintype "bidirectional"))
      (node (ref "J4") (pin "B7") (pinfunction "DN2_B7") (pintype "bidirectional"))
    )
    (net (code "12") (name "DP") (class "Default")
      (node (ref "D3") (pin "3") (pinfunction "I/O2_1_3") (pintype "bidirectional"))
      (node (ref "J4") (pin "A6") (pinfunction "DP1_A6") (pintype "bidirectional"))
      (node (ref "J4") (pin "B6") (pinfunction "DP2_B6") (pintype "bidirectional"))
    )
    (net (code "13") (name "EPD_3V3") (class "Default")
      (node (ref "C1-EP-DR") (pin "1") (pinfunction "1_1") (pintype "passive"))
      (node (ref "EPD_C5") (pin "2") (pinfunction "2_2") (pintype "passive"))
      (node (ref "J1") (pin "15") (pinfunction "15_15") (pintype "bidirectional"))
      (node (ref "J1") (pin "16") (pinfunction "16_16") (pintype "bidirectional"))
      (node (ref "L5") (pin "2") (pinfunction "2_2") (pintype "passive"))
      (node (ref "Q1") (pin "3") (pinfunction "D_3") (pintype "bidirectional"))
    )
    (net (code "14") (name "EPD_BUSY") (class "Default")
      (node (ref "J1") (pin "9") (pinfunction "9_9") (pintype "bidirectional"))
      (node (ref "U1") (pin "P$AD12") (pinfunction "P0.17_P$AD12") (pintype "bidirectional"))
    )
    (net (code "15") (name "EPD_CS") (class "Default")
      (node (ref "J1") (pin "12") (pinfunction "12_12") (pintype "bidirectional"))
      (node (ref "U1") (pin "P$K2") (pinfunction "P0.05/AIN3_P$K2") (pintype "bidirectional"))
    )
    (net (code "16") (name "EPD_DC") (class "Default")
      (node (ref "J1") (pin "11") (pinfunction "11_11") (pintype "bidirectional"))
      (node (ref "U1") (pin "P$AD10") (pinfunction "P0.15_P$AD10") (pintype "bidirectional"))
    )
    (net (code "17") (name "EPD_RST") (class "Default")
      (node (ref "J1") (pin "10") (pinfunction "10_10") (pintype "bidirectional"))
      (node (ref "U1") (pin "P$AC11") (pinfunction "P0.16_P$AC11") (pintype "bidirectional"))
    )
    (net (code "18") (name "GDR") (class "Default")
      (node (ref "J1") (pin "2") (pinfunction "2_2") (pintype "bidirectional"))
      (node (ref "Q3") (pin "1") (pinfunction "G_1") (pintype "bidirectional"))
      (node (ref "R2_EP_DR") (pin "2") (pinfunction "2_2") (pintype "bidirectional"))
    )
    (net (code "19") (name "GND") (class "Default")
      (node (ref "C1") (pin "2") (pinfunction "2_2") (pintype "passive"))
      (node (ref "C1-EP-DR") (pin "2") (pinfunction "2_2") (pintype "passive"))
      (node (ref "C10") (pin "1") (pinfunction "1_1") (pintype "passive"))
      (node (ref "C11") (pin "1") (pinfunction "1_1") (pintype "passive"))
      (node (ref "C12") (pin "2") (pinfunction "2_2") (pintype "passive"))
      (node (ref "C13") (pin "2") (pinfunction "2_2") (pintype "passive"))
      (node (ref "C14") (pin "2") (pinfunction "2_2") (pintype "passive"))
      (node (ref "C15") (pin "2") (pinfunction "2_2") (pintype "passive"))
      (node (ref "C16") (pin "2") (pinfunction "2_2") (pintype "passive"))
      (node (ref "C17") (pin "1") (pinfunction "1_1") (pintype "passive"))
      (node (ref "C18") (pin "1") (pinfunction "1_1") (pintype "passive"))
      (node (ref "C19") (pin "2") (pinfunction "2_2") (pintype "passive"))
      (node (ref "C2") (pin "2") (pinfunction "2_2") (pintype "passive"))
      (node (ref "C20") (pin "2") (pinfunction "2_2") (pintype "passive"))
      (node (ref "C21") (pin "2") (pinfunction "2_2") (pintype "passive"))
      (node (ref "C22") (pin "2") (pinfunction "2_2") (pintype "passive"))
      (node (ref "C23") (pin "1") (pinfunction "1_1") (pintype "passive"))
      (node (ref "C24") (pin "1") (pinfunction "1_1") (pintype "passive"))
      (node (ref "C25") (pin "2") (pinfunction "2_2") (pintype "passive"))
      (node (ref "C27") (pin "2") (pinfunction "2_2") (pintype "passive"))
      (node (ref "C29") (pin "2") (pinfunction "2_2") (pintype "passive"))
      (node (ref "C3") (pin "1") (pinfunction "1_1") (pintype "passive"))
      (node (ref "C30") (pin "2") (pinfunction "2_2") (pintype "passive"))
      (node (ref "C31") (pin "2") (pinfunction "2_2") (pintype "passive"))
      (node (ref "C32") (pin "2") (pinfunction "2_2") (pintype "passive"))
      (node (ref "C33") (pin "2") (pinfunction "2_2") (pintype "passive"))
      (node (ref "C34") (pin "2") (pinfunction "2_2") (pintype "passive"))
      (node (ref "C37") (pin "2") (pinfunction "2_2") (pintype "passive"))
      (node (ref "C38") (pin "2") (pinfunction "2_2") (pintype "passive"))
      (node (ref "C39") (pin "2") (pinfunction "2_2") (pintype "passive"))
      (node (ref "C4") (pin "1") (pinfunction "1_1") (pintype "passive"))
      (node (ref "C42") (pin "2") (pinfunction "2_2") (pintype "passive"))
      (node (ref "C43") (pin "2") (pinfunction "2_2") (pintype "passive"))
      (node (ref "C5") (pin "2") (pinfunction "2_2") (pintype "passive"))
      (node (ref "C6") (pin "2") (pinfunction "2_2") (pintype "passive"))
      (node (ref "C7") (pin "2") (pinfunction "2_2") (pintype "passive"))
      (node (ref "C8") (pin "1") (pinfunction "1_1") (pintype "passive"))
      (node (ref "C9") (pin "1") (pinfunction "1_1") (pintype "passive"))
      (node (ref "D3") (pin "2") (pinfunction "GND_2") (pintype "bidirectional"))
      (node (ref "D4") (pin "1") (pinfunction "K_1") (pintype "bidirectional"))
      (node (ref "EPD_C1") (pin "1") (pinfunction "1_1") (pintype "passive"))
      (node (ref "EPD_C10") (pin "1") (pinfunction "1_1") (pintype "passive"))
      (node (ref "EPD_C11") (pin "1") (pinfunction "1_1") (pintype "passive"))
      (node (ref "EPD_C12") (pin "1") (pinfunction "1_1") (pintype "passive"))
      (node (ref "EPD_C2") (pin "1") (pinfunction "1_1") (pintype "passive"))
      (node (ref "EPD_C5") (pin "1") (pinfunction "1_1") (pintype "passive"))
      (node (ref "EPD_C6") (pin "1") (pinfunction "1_1") (pintype "passive"))
      (node (ref "EPD_C7") (pin "1") (pinfunction "1_1") (pintype "passive"))
      (node (ref "EPD_C8") (pin "1") (pinfunction "1_1") (pintype "passive"))
      (node (ref "EPD_C9") (pin "1") (pinfunction "1_1") (pintype "passive"))
      (node (ref "IC1") (pin "D2") (pinfunction "GND_D2") (pintype "bidirectional"))
      (node (ref "IC2") (pin "B1") (pinfunction "VSEL_B1") (pintype "bidirectional"))
      (node (ref "IC2") (pin "C1") (pinfunction "AGND_C1") (pintype "bidirectional"))
      (node (ref "IC2") (pin "C2") (pinfunction "PGND_1_C2") (pintype "bidirectional"))
      (node (ref "IC2") (pin "C3") (pinfunction "PGND_2_C3") (pintype "bidirectional"))
      (node (ref "IC3") (pin "8") (pinfunction "GNDIO_8") (pintype "bidirectional"))
      (node (ref "IC3") (pin "9") (pinfunction "GND_9") (pintype "bidirectional"))
      (node (ref "IC4") (pin "B1") (pinfunction "IN/TRIG_B1") (pintype "bidirectional"))
      (node (ref "IC4") (pin "B3") (pinfunction "GND_B3") (pintype "bidirectional"))
      (node (ref "J1") (pin "17") (pinfunction "17_17") (pintype "bidirectional"))
      (node (ref "J1") (pin "8") (pinfunction "8_8") (pintype "bidirectional"))
      (node (ref "J1") (pin "MP1") (pinfunction "MP1_MP1") (pintype "bidirectional"))
      (node (ref "J1") (pin "MP2") (pinfunction "MP2_MP2") (pintype "bidirectional"))
      (node (ref "J2") (pin "3") (pinfunction "3_3") (pintype "bidirectional"))
      (node (ref "J2") (pin "5") (pinfunction "5_5") (pintype "bidirectional"))
      (node (ref "J4") (pin "A12_B1") (pinfunction "GND_A12_B1") (pintype "power_in"))
      (node (ref "J4") (pin "A1_B12") (pinfunction "GND_A1_B12") (pintype "power_in"))
      (node (ref "J4") (pin "SH1") (pinfunction "SHIELD_SH1") (pintype "passive"))
      (node (ref "J4") (pin "SH2") (pinfunction "SHIELD_SH2") (pintype "passive"))
      (node (ref "J4") (pin "SH3") (pinfunction "SHIELD_SH3") (pintype "passive"))
      (node (ref "J4") (pin "SH4") (pinfunction "SHIELD_SH4") (pintype "passive"))
      (node (ref "R1_USB") (pin "1") (pinfunction "1_1") (pintype "bidirectional"))
      (node (ref "R2_EP_DR") (pin "1") (pinfunction "1_1") (pintype "bidirectional"))
      (node (ref "R2_USB") (pin "2") (pinfunction "2_2") (pintype "bidirectional"))
      (node (ref "R3") (pin "1") (pinfunction "1_1") (pintype "bidirectional"))
      (node (ref "R9") (pin "1") (pinfunction "1_1") (pintype "bidirectional"))
      (node (ref "R_TYPE_SEL") (pin "1") (pinfunction "1_1") (pintype "bidirectional"))
      (node (ref "SJ1") (pin "1") (pinfunction "1_1") (pintype "passive"))
      (node (ref "SW_DN") (pin "1") (pinfunction "1_1") (pintype "passive"))
      (node (ref "SW_ENT") (pin "1") (pinfunction "1_1") (pintype "passive"))
      (node (ref "SW_UP") (pin "1") (pinfunction "1_1") (pintype "passive"))
      (node (ref "TP_BAT_GND") (pin "TP") (pinfunction "TP_TP") (pintype "input"))
      (node (ref "TP_GND") (pin "TP") (pinfunction "TP_TP") (pintype "input"))
      (node (ref "U1") (pin "P$74") (pinfunction "VSS_PAD_P$74") (pintype "bidirectional"))
      (node (ref "U1") (pin "P$75") (pinfunction "VSS_PAD_P$75") (pintype "bidirectional"))
      (node (ref "U1") (pin "P$76") (pinfunction "VSS_PAD_P$76") (pintype "bidirectional"))
      (node (ref "U1") (pin "P$77") (pinfunction "VSS_PAD_P$77") (pintype "bidirectional"))
      (node (ref "U1") (pin "P$78") (pinfunction "VSS_PAD_P$78") (pintype "bidirectional"))
      (node (ref "U1") (pin "P$79") (pinfunction "VSS_PAD_P$79") (pintype "bidirectional"))
      (node (ref "U1") (pin "P$80") (pinfunction "VSS_PAD_P$80") (pintype "bidirectional"))
      (node (ref "U1") (pin "P$81") (pinfunction "VSS_PAD_P$81") (pintype "bidirectional"))
      (node (ref "U1") (pin "P$82") (pinfunction "VSS_PAD_P$82") (pintype "bidirectional"))
      (node (ref "U1") (pin "P$83") (pinfunction "VSS_PAD_P$83") (pintype "bidirectional"))
      (node (ref "U1") (pin "P$84") (pinfunction "VSS_PAD_P$84") (pintype "bidirectional"))
      (node (ref "U1") (pin "P$85") (pinfunction "VSS_PAD_P$85") (pintype "bidirectional"))
      (node (ref "U1") (pin "P$86") (pinfunction "VSS_PAD_P$86") (pintype "bidirectional"))
      (node (ref "U1") (pin "P$87") (pinfunction "VSS_PAD_P$87") (pintype "bidirectional"))
      (node (ref "U1") (pin "P$88") (pinfunction "VSS_PAD_P$88") (pintype "bidirectional"))
      (node (ref "U1") (pin "P$89") (pinfunction "VSS_PAD_P$89") (pintype "bidirectional"))
      (node (ref "U1") (pin "P$90") (pinfunction "VSS_PAD_P$90") (pintype "bidirectional"))
      (node (ref "U1") (pin "P$B7") (pinfunction "VSS_P$B7") (pintype "power_in"))
      (node (ref "U1") (pin "P$F23") (pinfunction "VSS_PA_P$F23") (pintype "bidirectional"))
      (node (ref "U3") (pin "1") (pinfunction "CTG_1") (pintype "power_in"))
      (node (ref "U3") (pin "4") (pinfunction "GND_4") (pintype "power_in"))
      (node (ref "U3") (pin "6") (pinfunction "QSTRT_6") (pintype "input"))
      (node (ref "U3") (pin "9") (pinfunction "EP_9") (pintype "power_in"))
      (node (ref "X1") (pin "2") (pinfunction "2_2") (pintype "passive"))
      (node (ref "X1") (pin "4") (pinfunction "4_4") (pintype "passive"))
    )
    (net (code "20") (name "HAPTIC_EN") (class "Default")
      (node (ref "IC4") (pin "A1") (pinfunction "EN_A1") (pintype "bidirectional"))
      (node (ref "U1") (pin "P$U1") (pinfunction "P0.12_P$U1") (pintype "bidirectional"))
    )
    (net (code "21") (name "IMU_INT1") (class "Default")
      (node (ref "IC3") (pin "5") (pinfunction "INT1_5") (pintype "bidirectional"))
      (node (ref "U1") (pin "P$N1") (pinfunction "P0.08_P$N1") (pintype "bidirectional"))
    )
    (net (code "22") (name "IMU_INT2") (class "Default")
      (node (ref "IC3") (pin "6") (pinfunction "INT2_6") (pintype "bidirectional"))
      (node (ref "U1") (pin "P$P2") (pinfunction "P1.08_P$P2") (pintype "bidirectional"))
    )
    (net (code "23") (name "LX1") (class "Default")
      (node (ref "IC2") (pin "B2") (pinfunction "SW1_1_B2") (pintype "bidirectional"))
      (node (ref "IC2") (pin "B3") (pinfunction "SW1_2_B3") (pintype "bidirectional"))
      (node (ref "L7") (pin "1") (pinfunction "1_1") (pintype "bidirectional"))
    )
    (net (code "24") (name "LX2") (class "Default")
      (node (ref "IC2") (pin "D2") (pinfunction "SW2_1_D2") (pintype "bidirectional"))
      (node (ref "IC2") (pin "D3") (pinfunction "SW2_2_D3") (pintype "bidirectional"))
      (node (ref "L7") (pin "2") (pinfunction "2_2") (pintype "bidirectional"))
    )
    (net (code "25") (name "MOSI") (class "Default")
      (node (ref "J1") (pin "14") (pinfunction "14_14") (pintype "bidirectional"))
      (node (ref "U1") (pin "P$B13") (pinfunction "P0.03/AIN1_P$B13") (pintype "bidirectional"))
    )
    (net (code "26") (name "Net-(D2-K)") (class "Default")
      (node (ref "C2-EP-DR") (pin "1") (pinfunction "1_1") (pintype "passive"))
      (node (ref "D2") (pin "1") (pinfunction "K_1") (pintype "bidirectional"))
      (node (ref "D4") (pin "2") (pinfunction "A_2") (pintype "bidirectional"))
    )
    (net (code "27") (name "Net-(D5-A)") (class "Default")
      (node (ref "C2-EP-DR") (pin "2") (pinfunction "2_2") (pintype "passive"))
      (node (ref "D5") (pin "2") (pinfunction "A_2") (pintype "bidirectional"))
      (node (ref "L5") (pin "1") (pinfunction "1_1") (pintype "passive"))
      (node (ref "Q3") (pin "3") (pinfunction "D_3") (pintype "bidirectional"))
    )
    (net (code "28") (name "Net-(EPD_C1-Pad2)") (class "Default")
      (node (ref "EPD_C1") (pin "2") (pinfunction "2_2") (pintype "passive"))
      (node (ref "J1") (pin "5") (pinfunction "5_5") (pintype "bidirectional"))
    )
    (net (code "29") (name "Net-(EPD_C2-Pad2)") (class "Default")
      (node (ref "EPD_C2") (pin "2") (pinfunction "2_2") (pintype "passive"))
      (node (ref "J1") (pin "4") (pinfunction "4_4") (pintype "bidirectional"))
    )
    (net (code "30") (name "Net-(EPD_C6-Pad2)") (class "Default")
      (node (ref "EPD_C6") (pin "2") (pinfunction "2_2") (pintype "passive"))
      (node (ref "J1") (pin "18") (pinfunction "18_18") (pintype "bidirectional"))
    )
    (net (code "31") (name "Net-(EPD_C7-Pad2)") (class "Default")
      (node (ref "EPD_C7") (pin "2") (pinfunction "2_2") (pintype "passive"))
      (node (ref "J1") (pin "19") (pinfunction "19_19") (pintype "bidirectional"))
    )
    (net (code "32") (name "Net-(EPD_C8-Pad2)") (class "Default")
      (node (ref "EPD_C8") (pin "2") (pinfunction "2_2") (pintype "passive"))
      (node (ref "J1") (pin "20") (pinfunction "20_20") (pintype "bidirectional"))
    )
    (net (code "33") (name "Net-(EPD_C10-Pad2)") (class "Default")
      (node (ref "EPD_C10") (pin "2") (pinfunction "2_2") (pintype "passive"))
      (node (ref "J1") (pin "22") (pinfunction "22_22") (pintype "bidirectional"))
    )
    (net (code "34") (name "Net-(EPD_C12-Pad2)") (class "Default")
      (node (ref "EPD_C12") (pin "2") (pinfunction "2_2") (pintype "passive"))
      (node (ref "J1") (pin "24") (pinfunction "24_24") (pintype "bidirectional"))
    )
    (net (code "35") (name "Net-(IC1-TS{slash}MR)") (class "Default")
      (node (ref "IC1") (pin "D1") (pinfunction "TS/MR_D1") (pintype "bidirectional"))
      (node (ref "R9") (pin "2") (pinfunction "2_2") (pintype "bidirectional"))
    )
    (net (code "36") (name "Net-(IC2-SCL)") (class "Default")
      (node (ref "IC2") (pin "D1") (pinfunction "SCL_D1") (pintype "bidirectional"))
      (node (ref "R4") (pin "2") (pinfunction "2_2") (pintype "bidirectional"))
    )
    (net (code "37") (name "Net-(IC2-SDA)") (class "Default")
      (node (ref "IC2") (pin "E1") (pinfunction "SDA_E1") (pintype "bidirectional"))
      (node (ref "R2") (pin "2") (pinfunction "2_2") (pintype "bidirectional"))
    )
    (net (code "38") (name "Net-(IC3-SDO)") (class "Default")
      (node (ref "IC3") (pin "1") (pinfunction "SDO_1") (pintype "bidirectional"))
      (node (ref "R3") (pin "2") (pinfunction "2_2") (pintype "bidirectional"))
    )
    (net (code "39") (name "Net-(IC4-REG)") (class "Default")
      (node (ref "C32") (pin "1") (pinfunction "1_1") (pintype "passive"))
      (node (ref "IC4") (pin "A2") (pinfunction "REG_A2") (pintype "bidirectional"))
    )
    (net (code "40") (name "Net-(J4-CC1)") (class "Default")
      (node (ref "J4") (pin "A5") (pinfunction "CC1_A5") (pintype "bidirectional"))
      (node (ref "R1_USB") (pin "2") (pinfunction "2_2") (pintype "bidirectional"))
    )
    (net (code "41") (name "Net-(J4-CC2)") (class "Default")
      (node (ref "J4") (pin "B5") (pinfunction "CC2_B5") (pintype "bidirectional"))
      (node (ref "R2_USB") (pin "1") (pinfunction "1_1") (pintype "bidirectional"))
    )
    (net (code "42") (name "Net-(L2-Pad2)") (class "Default")
      (node (ref "L2") (pin "2") (pinfunction "2_2") (pintype "passive"))
      (node (ref "L3") (pin "1") (pinfunction "1_1") (pintype "passive"))
    )
    (net (code "43") (name "Net-(R1_EP_DR-Pad1)") (class "Default")
      (node (ref "R1_EP_DR") (pin "1") (pinfunction "1_1") (pintype "bidirectional"))
      (node (ref "R_TYPE_SEL") (pin "2") (pinfunction "2_2") (pintype "bidirectional"))
      (node (ref "SJ1") (pin "2") (pinfunction "2_2") (pintype "passive"))
    )
    (net (code "44") (name "Net-(U1-ANT)") (class "Default")
      (node (ref "C3") (pin "2") (pinfunction "2_2") (pintype "passive"))
      (node (ref "L1") (pin "1") (pinfunction "1_1") (pintype "passive"))
      (node (ref "U1") (pin "P$H23") (pinfunction "ANT_P$H23") (pintype "bidirectional"))
    )
    (net (code "45") (name "Net-(U1-DCC)") (class "Default")
      (node (ref "L2") (pin "1") (pinfunction "1_1") (pintype "passive"))
      (node (ref "U1") (pin "P$B3") (pinfunction "DCC_P$B3") (pintype "output"))
    )
    (net (code "46") (name "Net-(U1-DEC2)") (class "Default")
      (node (ref "C13") (pin "1") (pinfunction "1_1") (pintype "passive"))
      (node (ref "U1") (pin "P$A18") (pinfunction "DEC2_P$A18") (pintype "bidirectional"))
    )
    (net (code "47") (name "Net-(U1-DEC3V3)") (class "Default")
      (node (ref "C20") (pin "1") (pinfunction "1_1") (pintype "passive"))
      (node (ref "U1") (pin "P$AC5") (pinfunction "DEC3V3_P$AC5") (pintype "bidirectional"))
    )
    (net (code "48") (name "Net-(U1-DEC5)") (class "Default")
      (node (ref "C9") (pin "2") (pinfunction "2_2") (pintype "passive"))
      (node (ref "U1") (pin "P$N24") (pinfunction "DEC5_P$N24") (pintype "bidirectional"))
    )
    (net (code "49") (name "Net-(U1-XC1)") (class "Default")
      (node (ref "C1") (pin "1") (pinfunction "1_1") (pintype "passive"))
      (node (ref "U1") (pin "P$B24") (pinfunction "XC1_P$B24") (pintype "input"))
      (node (ref "X1") (pin "1") (pinfunction "1_1") (pintype "passive"))
    )
    (net (code "50") (name "Net-(U1-XC2)") (class "Default")
      (node (ref "C2") (pin "1") (pinfunction "1_1") (pintype "passive"))
      (node (ref "U1") (pin "P$A23") (pinfunction "XC2_P$A23") (pintype "output"))
      (node (ref "X1") (pin "3") (pinfunction "3_3") (pintype "passive"))
    )
    (net (code "51") (name "OUT+") (class "Default")
      (node (ref "IC4") (pin "A3") (pinfunction "OUT+_A3") (pintype "bidirectional"))
      (node (ref "TP_OP") (pin "TP") (pinfunction "TP_TP") (pintype "input"))
    )
    (net (code "52") (name "OUT-") (class "Default")
      (node (ref "IC4") (pin "C3") (pinfunction "OUT-_C3") (pintype "bidirectional"))
      (node (ref "TP_ON") (pin "TP") (pinfunction "TP_TP") (pintype "input"))
    )
    (net (code "53") (name "P0.04") (class "Default")
      (node (ref "U1") (pin "P$J1") (pinfunction "P0.04/AIN2_P$J1") (pintype "bidirectional"))
    )
    (net (code "54") (name "P0.09") (class "Default")
      (node (ref "U1") (pin "P$L24") (pinfunction "P0.09/NFC1_P$L24") (pintype "bidirectional"))
    )
    (net (code "55") (name "P0.13") (class "Default")
      (node (ref "C30") (pin "1") (pinfunction "1_1") (pintype "passive"))
      (node (ref "R5") (pin "1") (pinfunction "1_1") (pintype "bidirectional"))
      (node (ref "SW_UP") (pin "2") (pinfunction "2_2") (pintype "passive"))
      (node (ref "U1") (pin "P$AD8") (pinfunction "P0.13_P$AD8") (pintype "bidirectional"))
    )
    (net (code "56") (name "P0.14") (class "Default")
      (node (ref "C31") (pin "1") (pinfunction "1_1") (pintype "passive"))
      (node (ref "R8") (pin "1") (pinfunction "1_1") (pintype "bidirectional"))
      (node (ref "SW_ENT") (pin "2") (pinfunction "2_2") (pintype "passive"))
      (node (ref "U1") (pin "P$AC9") (pinfunction "P0.14_P$AC9") (pintype "bidirectional"))
    )
    (net (code "57") (name "P0.19") (class "Default")
      (node (ref "U1") (pin "P$AC15") (pinfunction "P0.19_P$AC15") (pintype "bidirectional"))
    )
    (net (code "58") (name "P0.20") (class "Default")
      (node (ref "U1") (pin "P$AD16") (pinfunction "P0.20_P$AD16") (pintype "bidirectional"))
    )
    (net (code "59") (name "P0.21") (class "Default")
      (node (ref "U1") (pin "P$AC17") (pinfunction "P0.21_P$AC17") (pintype "bidirectional"))
    )
    (net (code "60") (name "P0.22") (class "Default")
      (node (ref "U1") (pin "P$AD18") (pinfunction "P0.22_P$AD18") (pintype "bidirectional"))
    )
    (net (code "61") (name "P0.23") (class "Default")
      (node (ref "U1") (pin "P$AC19") (pinfunction "P0.23_P$AC19") (pintype "bidirectional"))
    )
    (net (code "62") (name "P0.24") (class "Default")
      (node (ref "U1") (pin "P$AD20") (pinfunction "P0.24_P$AD20") (pintype "bidirectional"))
    )
    (net (code "63") (name "P0.25") (class "Default")
      (node (ref "U1") (pin "P$AC21") (pinfunction "P0.25_P$AC21") (pintype "bidirectional"))
    )
    (net (code "64") (name "P0.26") (class "Default")
      (node (ref "U1") (pin "P$G1") (pinfunction "P0.26_P$G1") (pintype "bidirectional"))
    )
    (net (code "65") (name "P0.27") (class "Default")
      (node (ref "U1") (pin "P$H2") (pinfunction "P0.27_P$H2") (pintype "bidirectional"))
    )
    (net (code "66") (name "P0.28") (class "Default")
      (node (ref "U1") (pin "P$B11") (pinfunction "P0.28/AIN4_P$B11") (pintype "bidirectional"))
    )
    (net (code "67") (name "P0.29") (class "Default")
      (node (ref "U1") (pin "P$A10") (pinfunction "P0.29/AIN5_P$A10") (pintype "bidirectional"))
    )
    (net (code "68") (name "P0.30") (class "Default")
      (node (ref "U1") (pin "P$B9") (pinfunction "P0.30/AIN6_P$B9") (pintype "bidirectional"))
    )
    (net (code "69") (name "P0.31") (class "Default")
      (node (ref "U1") (pin "P$A8") (pinfunction "P0.31/AIN7_P$A8") (pintype "bidirectional"))
    )
    (net (code "70") (name "P1.01") (class "Default")
      (node (ref "Q1") (pin "1") (pinfunction "G_1") (pintype "bidirectional"))
      (node (ref "R_PWR_EPD") (pin "1") (pinfunction "1_1") (pintype "bidirectional"))
      (node (ref "U1") (pin "P$Y23") (pinfunction "P1.01_P$Y23") (pintype "bidirectional"))
    )
    (net (code "71") (name "P1.02") (class "Default")
      (node (ref "C29") (pin "1") (pinfunction "1_1") (pintype "passive"))
      (node (ref "R7") (pin "1") (pinfunction "1_1") (pintype "bidirectional"))
      (node (ref "SW_DN") (pin "2") (pinfunction "2_2") (pintype "passive"))
      (node (ref "U1") (pin "P$W24") (pinfunction "P1.02_P$W24") (pintype "bidirectional"))
    )
    (net (code "72") (name "P1.03") (class "Default")
      (node (ref "U1") (pin "P$V23") (pinfunction "P1.03_P$V23") (pintype "bidirectional"))
    )
    (net (code "73") (name "P1.04") (class "Default")
      (node (ref "U1") (pin "P$U24") (pinfunction "P1.04_P$U24") (pintype "bidirectional"))
    )
    (net (code "74") (name "P1.05") (class "Default")
      (node (ref "U1") (pin "P$T23") (pinfunction "P1.05_P$T23") (pintype "bidirectional"))
    )
    (net (code "75") (name "P1.06") (class "Default")
      (node (ref "U1") (pin "P$R24") (pinfunction "P1.06_P$R24") (pintype "bidirectional"))
    )
    (net (code "76") (name "P1.07") (class "Default")
      (node (ref "U1") (pin "P$P23") (pinfunction "P1.07_P$P23") (pintype "bidirectional"))
    )
    (net (code "77") (name "P1.09") (class "Default")
      (node (ref "U1") (pin "P$R1") (pinfunction "P1.09_P$R1") (pintype "bidirectional"))
    )
    (net (code "78") (name "P1.10") (class "Default")
      (node (ref "U1") (pin "P$A20") (pinfunction "P1.10_P$A20") (pintype "bidirectional"))
    )
    (net (code "79") (name "P1.11") (class "Default")
      (node (ref "U1") (pin "P$B19") (pinfunction "P1.11_P$B19") (pintype "bidirectional"))
    )
    (net (code "80") (name "P1.12") (class "Default")
      (node (ref "U1") (pin "P$B17") (pinfunction "P1.12_P$B17") (pintype "bidirectional"))
    )
    (net (code "81") (name "P1.13") (class "Default")
      (node (ref "U1") (pin "P$A16") (pinfunction "P1.13_P$A16") (pintype "bidirectional"))
    )
    (net (code "82") (name "P1.14") (class "Default")
      (node (ref "U1") (pin "P$B15") (pinfunction "P1.14_P$B15") (pintype "bidirectional"))
    )
    (net (code "83") (name "P1.15") (class "Default")
      (node (ref "U1") (pin "P$A14") (pinfunction "P1.15_P$A14") (pintype "bidirectional"))
    )
    (net (code "84") (name "PMIC_INT") (class "Default")
      (node (ref "IC1") (pin "A1") (pinfunction "~{INT}_A1") (pintype "bidirectional"))
      (node (ref "U1") (pin "P$T2") (pinfunction "P0.11_P$T2") (pintype "bidirectional"))
    )
    (net (code "85") (name "PREVGH") (class "Default")
      (node (ref "D5") (pin "1") (pinfunction "K_1") (pintype "bidirectional"))
      (node (ref "EPD_C9") (pin "2") (pinfunction "2_2") (pintype "passive"))
      (node (ref "J1") (pin "21") (pinfunction "21_21") (pintype "bidirectional"))
    )
    (net (code "86") (name "PREVGL") (class "Default")
      (node (ref "D2") (pin "2") (pinfunction "A_2") (pintype "bidirectional"))
      (node (ref "EPD_C11") (pin "2") (pinfunction "2_2") (pintype "passive"))
      (node (ref "J1") (pin "23") (pinfunction "23_23") (pintype "bidirectional"))
    )
    (net (code "87") (name "RESE") (class "Default")
      (node (ref "J1") (pin "3") (pinfunction "3_3") (pintype "bidirectional"))
      (node (ref "Q3") (pin "2") (pinfunction "S_2") (pintype "bidirectional"))
      (node (ref "R1_EP_DR") (pin "2") (pinfunction "2_2") (pintype "bidirectional"))
    )
    (net (code "88") (name "RESET") (class "Default")
      (node (ref "J2") (pin "6") (pinfunction "6_6") (pintype "bidirectional"))
      (node (ref "TP_RESET") (pin "TP") (pinfunction "TP_TP") (pintype "input"))
      (node (ref "U1") (pin "P$AC13") (pinfunction "P0.18/RESET_P$AC13") (pintype "bidirectional"))
    )
    (net (code "89") (name "SCK") (class "Default")
      (node (ref "J1") (pin "13") (pinfunction "13_13") (pintype "bidirectional"))
      (node (ref "U1") (pin "P$A12") (pinfunction "P0.02/AIN0_P$A12") (pintype "bidirectional"))
    )
    (net (code "90") (name "SCL") (class "Default")
      (node (ref "IC1") (pin "B1") (pinfunction "SCL_B1") (pintype "bidirectional"))
      (node (ref "IC3") (pin "12") (pinfunction "SCX_12") (pintype "bidirectional"))
      (node (ref "IC4") (pin "C1") (pinfunction "SCL_C1") (pintype "bidirectional"))
      (node (ref "R17") (pin "2") (pinfunction "2_2") (pintype "bidirectional"))
      (node (ref "R4") (pin "1") (pinfunction "1_1") (pintype "bidirectional"))
      (node (ref "TP_SCL") (pin "TP") (pinfunction "TP_TP") (pintype "input"))
      (node (ref "U1") (pin "P$M2") (pinfunction "P0.07_P$M2") (pintype "bidirectional"))
      (node (ref "U3") (pin "7") (pinfunction "SCL_7") (pintype "input"))
    )
    (net (code "91") (name "SDA") (class "Default")
      (node (ref "IC1") (pin "C1") (pinfunction "SDA_C1") (pintype "bidirectional"))
      (node (ref "IC3") (pin "2") (pinfunction "SDX_2") (pintype "bidirectional"))
      (node (ref "IC4") (pin "B2") (pinfunction "SDA_B2") (pintype "bidirectional"))
      (node (ref "R18") (pin "2") (pinfunction "2_2") (pintype "bidirectional"))
      (node (ref "R2") (pin "1") (pinfunction "1_1") (pintype "bidirectional"))
      (node (ref "TP_SDA") (pin "TP") (pinfunction "TP_TP") (pintype "input"))
      (node (ref "U1") (pin "P$L1") (pinfunction "P0.06_P$L1") (pintype "bidirectional"))
      (node (ref "U3") (pin "8") (pinfunction "SDA_8") (pintype "bidirectional"))
    )
    (net (code "92") (name "SWDCLK") (class "Default")
      (node (ref "J2") (pin "4") (pinfunction "4_4") (pintype "bidirectional"))
      (node (ref "TP_SWDCLK") (pin "TP") (pinfunction "TP_TP") (pintype "input"))
      (node (ref "U1") (pin "P$AA24") (pinfunction "SWDCLK_P$AA24") (pintype "input"))
    )
    (net (code "93") (name "SWDIO") (class "Default")
      (node (ref "J2") (pin "2") (pinfunction "2_2") (pintype "bidirectional"))
      (node (ref "TP_SWDIO") (pin "TP") (pinfunction "TP_TP") (pintype "input"))
      (node (ref "U1") (pin "P$AC24") (pinfunction "SWDIO_P$AC24") (pintype "bidirectional"))
    )
    (net (code "94") (name "SWO") (class "Default")
      (node (ref "TP_SWO") (pin "TP") (pinfunction "TP_TP") (pintype "input"))
      (node (ref "U1") (pin "P$AD22") (pinfunction "P1.00_P$AD22") (pintype "bidirectional"))
    )
    (net (code "95") (name "VBAT") (class "Default")
      (node (ref "C27") (pin "1") (pinfunction "1_1") (pintype "passive"))
      (node (ref "C37") (pin "1") (pinfunction "1_1") (pintype "passive"))
      (node (ref "IC1") (pin "C2") (pinfunction "BAT_C2") (pintype "bidirectional"))
      (node (ref "TP_VBAT") (pin "TP") (pinfunction "TP_TP") (pintype "input"))
      (node (ref "U3") (pin "2") (pinfunction "CELL_2") (pintype "power_in"))
      (node (ref "U3") (pin "3") (pinfunction "VDD_3") (pintype "power_in"))
    )
    (net (code "96") (name "VBUS") (class "Default")
      (node (ref "C21") (pin "1") (pinfunction "1_1") (pintype "passive"))
      (node (ref "C38") (pin "1") (pinfunction "1_1") (pintype "passive"))
      (node (ref "C42") (pin "1") (pinfunction "1_1") (pintype "passive"))
      (node (ref "C43") (pin "1") (pinfunction "1_1") (pintype "passive"))
      (node (ref "D3") (pin "5") (pinfunction "VBUS_5") (pintype "bidirectional"))
      (node (ref "IC1") (pin "A2") (pinfunction "IN_A2") (pintype "bidirectional"))
      (node (ref "J4") (pin "A4_B9") (pinfunction "VBUS_A4_B9") (pintype "power_in"))
      (node (ref "J4") (pin "A9_B4") (pinfunction "VBUS_A9_B4") (pintype "power_in"))
      (node (ref "U1") (pin "P$AD2") (pinfunction "VBUS_P$AD2") (pintype "power_in"))
    )
    (net (code "97") (name "VREG") (class "Default")
      (node (ref "C23") (pin "2") (pinfunction "2_2") (pintype "passive"))
      (node (ref "C24") (pin "2") (pinfunction "2_2") (pintype "passive"))
      (node (ref "C39") (pin "1") (pinfunction "1_1") (pintype "passive"))
      (node (ref "IC1") (pin "B2") (pinfunction "SYS_B2") (pintype "bidirectional"))
      (node (ref "IC2") (pin "A1") (pinfunction "EN_A1") (pintype "bidirectional"))
      (node (ref "IC2") (pin "A2") (pinfunction "VIN_1_A2") (pintype "bidirectional"))
      (node (ref "IC2") (pin "A3") (pinfunction "VIN_2_A3") (pintype "bidirectional"))
      (node (ref "TP_VREG") (pin "TP") (pinfunction "TP_TP") (pintype "input"))
    )
    (net (code "98") (name "unconnected-(ANT1-NC-Pad2)") (class "Default")
      (node (ref "ANT1") (pin "2") (pinfunction "NC_2") (pintype "no_connect"))
    )
    (net (code "99") (name "unconnected-(IC3-ASCL-Pad11)") (class "Default")
      (node (ref "IC3") (pin "11") (pinfunction "ASCL_11") (pintype "bidirectional"))
    )
    (net (code "100") (name "unconnected-(IC3-ASDA-Pad4)") (class "Default")
      (node (ref "IC3") (pin "4") (pinfunction "ASDA_4") (pintype "bidirectional"))
    )
    (net (code "101") (name "unconnected-(J1-Pad1)") (class "Default")
      (node (ref "J1") (pin "1") (pinfunction "1_1") (pintype "bidirectional"))
    )
    (net (code "102") (name "unconnected-(J1-Pad6)") (class "Default")
      (node (ref "J1") (pin "6") (pinfunction "6_6") (pintype "bidirectional"))
    )
    (net (code "103") (name "unconnected-(J1-Pad7)") (class "Default")
      (node (ref "J1") (pin "7") (pinfunction "7_7") (pintype "bidirectional"))
    )
    (net (code "104") (name "unconnected-(J4-SBU1-PadA8)") (class "Default")
      (node (ref "J4") (pin "A8") (pinfunction "SBU1_A8") (pintype "bidirectional"))
    )
    (net (code "105") (name "unconnected-(J4-SBU2-PadB8)") (class "Default")
      (node (ref "J4") (pin "B8") (pinfunction "SBU2_B8") (pintype "bidirectional"))
    )
    (net (code "106") (name "unconnected-(U1-DCCH-PadP$AB2)") (class "Default")
      (node (ref "U1") (pin "P$AB2") (pinfunction "DCCH_P$AB2") (pintype "bidirectional"))
    )
  )
)
